# testHeader.net
KiCad netlist of a schematic drawn in EAGLE
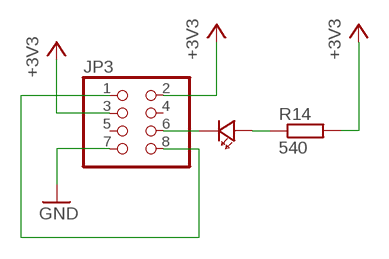
[diagram p0: schematic, sheet 1]

(export (version "E")
  (design (tool "Eeschema 10.0.6"))
  (components
    (comp (ref "JP3")
      (value "PINHD-2X4")
      (footprint "eagle-import:2X04")
      (libsource (lib "eagle-import") (part "PINHD-2X4"))
    )
    (comp (ref "LED-TX2")
      (value "LED0805")
      (footprint "eagle-import:CHIPLED_0805")
      (libsource (lib "eagle-import") (part "LED0805"))
    )
    (comp (ref "R14")
      (value "540")
      (footprint "eagle-import:R0805")
      (libsource (lib "eagle-import") (part "R-EU_R0805"))
    )
  )
  (nets
    (net (code "1") (name "+3V3") (class "Default")
      (node (ref "JP3") (pin "2") (pinfunction "2_2") (pintype "passive"))
      (node (ref "JP3") (pin "3") (pinfunction "3_3") (pintype "passive"))
      (node (ref "R14") (pin "2") (pinfunction "2_2") (pintype "passive"))
    )
    (net (code "2") (name "GND") (class "Default")
      (node (ref "JP3") (pin "7") (pinfunction "7_7") (pintype "passive"))
    )
    (net (code "3") (name "Net-(JP3-Pad1)") (class "Default")
      (node (ref "JP3") (pin "1") (pinfunction "1_1") (pintype "passive"))
      (node (ref "JP3") (pin "8") (pinfunction "8_8") (pintype "passive"))
    )
    (net (code "4") (name "Net-(JP3-Pad6)") (class "Default")
      (node (ref "JP3") (pin "6") (pinfunction "6_6") (pintype "passive"))
      (node (ref "LED-TX2") (pin "C") (pinfunction "C_C") (pintype "bidirectional"))
    )
    (net (code "5") (name "Net-(LED-TX2-PadA)") (class "Default")
      (node (ref "LED-TX2") (pin "A") (pinfunction "A_A") (pintype "bidirectional"))
      (node (ref "R14") (pin "1") (pinfunction "1_1") (pintype "passive"))
    )
    (net (code "6") (name "unconnected-(JP3-Pad4)") (class "Default")
      (node (ref "JP3") (pin "4") (pinfunction "4_4") (pintype "passive"))
    )
    (net (code "7") (name "unconnected-(JP3-Pad5)") (class "Default")
      (node (ref "JP3") (pin "5") (pinfunction "5_5") (pintype "passive"))
    )
  )
)
